# db9.net
KiCad netlist of a schematic drawn in EAGLE
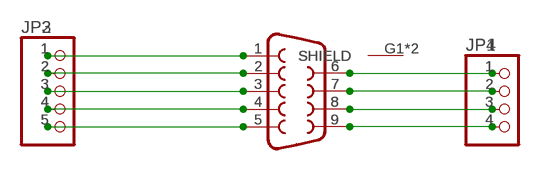
[diagram p0: schematic, sheet 1]

(export (version "E")
  (design (tool "Eeschema 10.0.6"))
  (components
    (comp (ref "J1")
      (value "DB9MALE")
      (footprint "eagle-import:DB9_MALE")
      (libsource (lib "eagle-import") (part "DB9MALE"))
    )
    (comp (ref "J2")
      (value "DB9MALE")
      (footprint "eagle-import:DB9_MALE")
      (libsource (lib "eagle-import") (part "DB9MALE"))
    )
    (comp (ref "JP1")
      (value "PINHD-1X4")
      (footprint "eagle-import:1X04")
      (libsource (lib "eagle-import") (part "PINHD-1X4"))
    )
    (comp (ref "JP2")
      (value "PINHD-1X5")
      (footprint "eagle-import:1X05")
      (libsource (lib "eagle-import") (part "PINHD-1X5"))
    )
    (comp (ref "JP3")
      (value "PINHD-1X5")
      (footprint "eagle-import:1X05")
      (libsource (lib "eagle-import") (part "PINHD-1X5"))
    )
    (comp (ref "JP4")
      (value "PINHD-1X4")
      (footprint "eagle-import:1X04")
      (libsource (lib "eagle-import") (part "PINHD-1X4"))
    )
  )
  (nets
    (net (code "1") (name "Net-(J1-Pad1)") (class "Default")
      (node (ref "J1") (pin "1") (pinfunction "1_1") (pintype "passive"))
      (node (ref "J2") (pin "1") (pinfunction "1_1") (pintype "passive"))
      (node (ref "JP2") (pin "1") (pinfunction "1_1") (pintype "passive"))
      (node (ref "JP3") (pin "1") (pinfunction "1_1") (pintype "passive"))
    )
    (net (code "2") (name "Net-(J1-Pad2)") (class "Default")
      (node (ref "J1") (pin "2") (pinfunction "2_2") (pintype "passive"))
      (node (ref "J2") (pin "2") (pinfunction "2_2") (pintype "passive"))
      (node (ref "JP2") (pin "2") (pinfunction "2_2") (pintype "passive"))
      (node (ref "JP3") (pin "2") (pinfunction "2_2") (pintype "passive"))
    )
    (net (code "3") (name "Net-(J1-Pad3)") (class "Default")
      (node (ref "J1") (pin "3") (pinfunction "3_3") (pintype "passive"))
      (node (ref "J2") (pin "3") (pinfunction "3_3") (pintype "passive"))
      (node (ref "JP2") (pin "3") (pinfunction "3_3") (pintype "passive"))
      (node (ref "JP3") (pin "3") (pinfunction "3_3") (pintype "passive"))
    )
    (net (code "4") (name "Net-(J1-Pad4)") (class "Default")
      (node (ref "J1") (pin "4") (pinfunction "4_4") (pintype "passive"))
      (node (ref "J2") (pin "4") (pinfunction "4_4") (pintype "passive"))
      (node (ref "JP2") (pin "4") (pinfunction "4_4") (pintype "passive"))
      (node (ref "JP3") (pin "4") (pinfunction "4_4") (pintype "passive"))
    )
    (net (code "5") (name "Net-(J1-Pad5)") (class "Default")
      (node (ref "J1") (pin "5") (pinfunction "5_5") (pintype "passive"))
      (node (ref "J2") (pin "5") (pinfunction "5_5") (pintype "passive"))
      (node (ref "JP2") (pin "5") (pinfunction "5_5") (pintype "passive"))
      (node (ref "JP3") (pin "5") (pinfunction "5_5") (pintype "passive"))
    )
    (net (code "6") (name "Net-(J1-Pad6)") (class "Default")
      (node (ref "J1") (pin "6") (pinfunction "6_6") (pintype "passive"))
      (node (ref "J2") (pin "6") (pinfunction "6_6") (pintype "passive"))
      (node (ref "JP1") (pin "1") (pinfunction "1_1") (pintype "passive"))
      (node (ref "JP4") (pin "1") (pinfunction "1_1") (pintype "passive"))
    )
    (net (code "7") (name "Net-(J1-Pad7)") (class "Default")
      (node (ref "J1") (pin "7") (pinfunction "7_7") (pintype "passive"))
      (node (ref "J2") (pin "7") (pinfunction "7_7") (pintype "passive"))
      (node (ref "JP1") (pin "2") (pinfunction "2_2") (pintype "passive"))
      (node (ref "JP4") (pin "2") (pinfunction "2_2") (pintype "passive"))
    )
    (net (code "8") (name "Net-(J1-Pad8)") (class "Default")
      (node (ref "J1") (pin "8") (pinfunction "8_8") (pintype "passive"))
      (node (ref "J2") (pin "8") (pinfunction "8_8") (pintype "passive"))
      (node (ref "JP1") (pin "3") (pinfunction "3_3") (pintype "passive"))
      (node (ref "JP4") (pin "3") (pinfunction "3_3") (pintype "passive"))
    )
    (net (code "9") (name "Net-(J1-Pad9)") (class "Default")
      (node (ref "J1") (pin "9") (pinfunction "9_9") (pintype "passive"))
      (node (ref "J2") (pin "9") (pinfunction "9_9") (pintype "passive"))
      (node (ref "JP1") (pin "4") (pinfunction "4_4") (pintype "passive"))
      (node (ref "JP4") (pin "4") (pinfunction "4_4") (pintype "passive"))
    )
    (net (code "10") (name "Net-(J1-SHIELD-PadG1)") (class "Default")
      (node (ref "J1") (pin "G1") (pinfunction "SHIELD_G1") (pintype "bidirectional"))
      (node (ref "J1") (pin "G2") (pinfunction "SHIELD_G2") (pintype "bidirectional"))
      (node (ref "J2") (pin "G1") (pinfunction "SHIELD_G1") (pintype "bidirectional"))
      (node (ref "J2") (pin "G2") (pinfunction "SHIELD_G2") (pintype "bidirectional"))
    )
  )
)
